# combined_breakout.net
KiCad netlist of a schematic drawn in EAGLE
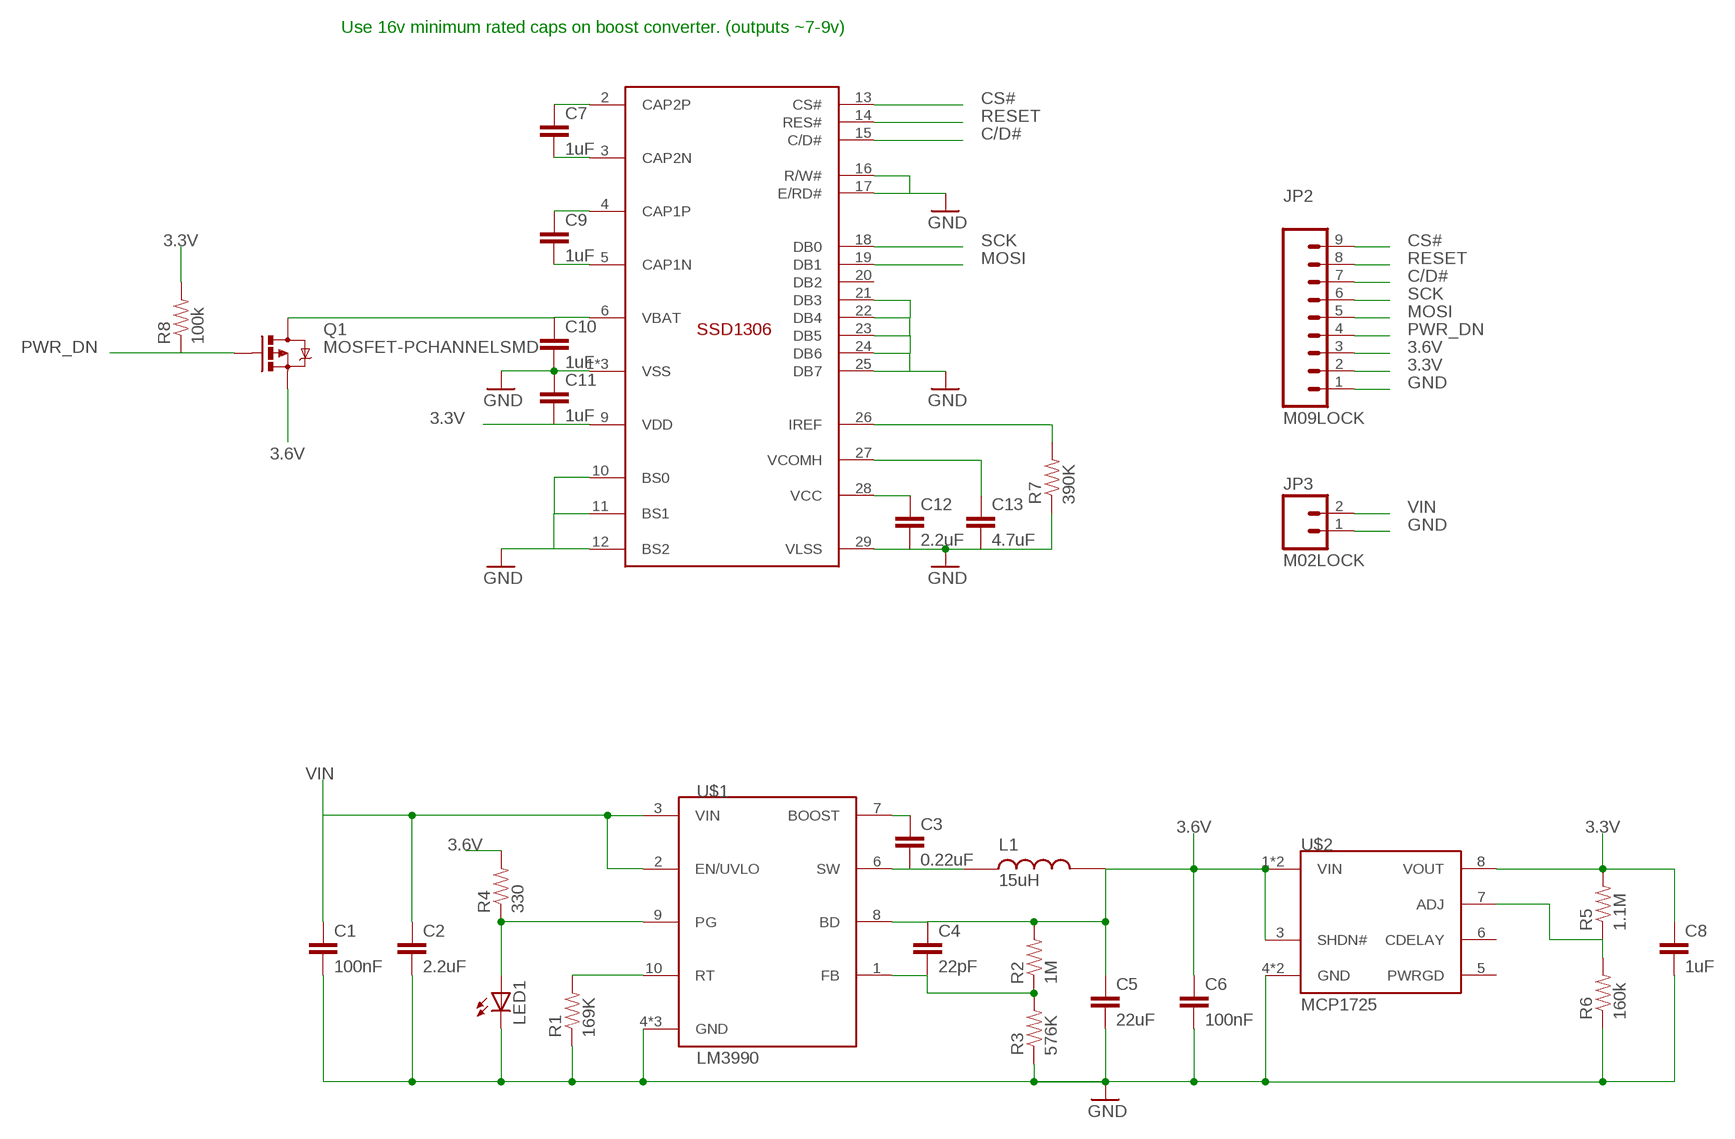
[diagram p0: schematic, sheet 1]

(export (version "E")
  (design (tool "Eeschema 10.0.6"))
  (components
    (comp (ref "C1")
      (value "100nF")
      (footprint "eagle-import:0603-CAP")
      (libsource (lib "eagle-import") (part "CAP0603-CAP"))
    )
    (comp (ref "C2")
      (value "2.2uF")
      (footprint "eagle-import:1206")
      (libsource (lib "eagle-import") (part "CAP1206"))
    )
    (comp (ref "C3")
      (value "0.22uF")
      (footprint "eagle-import:0603-CAP")
      (libsource (lib "eagle-import") (part "CAP0603-CAP"))
    )
    (comp (ref "C4")
      (value "22pF")
      (footprint "eagle-import:0603-CAP")
      (libsource (lib "eagle-import") (part "CAP0603-CAP"))
    )
    (comp (ref "C5")
      (value "22uF")
      (footprint "eagle-import:1206")
      (libsource (lib "eagle-import") (part "CAP1206"))
    )
    (comp (ref "C6")
      (value "100nF")
      (footprint "eagle-import:0603-CAP")
      (libsource (lib "eagle-import") (part "CAP0603-CAP"))
    )
    (comp (ref "C7")
      (value "1uF")
      (footprint "eagle-import:0402-S")
      (libsource (lib "eagle-import") (part "CAP0402-S"))
    )
    (comp (ref "C8")
      (value "1uF")
      (footprint "eagle-import:0603-CAP")
      (libsource (lib "eagle-import") (part "CAP0603-CAP"))
    )
    (comp (ref "C9")
      (value "1uF")
      (footprint "eagle-import:0402-S")
      (libsource (lib "eagle-import") (part "CAP0402-S"))
    )
    (comp (ref "C10")
      (value "1uF")
      (footprint "eagle-import:0402-S")
      (libsource (lib "eagle-import") (part "CAP0402-S"))
    )
    (comp (ref "C11")
      (value "1uF")
      (footprint "eagle-import:0402-S")
      (libsource (lib "eagle-import") (part "CAP0402-S"))
    )
    (comp (ref "C12")
      (value "2.2uF")
      (footprint "eagle-import:0402-S")
      (libsource (lib "eagle-import") (part "CAP0402-S"))
    )
    (comp (ref "C13")
      (value "4.7uF")
      (footprint "eagle-import:0402-S")
      (libsource (lib "eagle-import") (part "CAP0402-S"))
    )
    (comp (ref "JP2")
      (value "M09LOCK")
      (footprint "eagle-import:1X09_LOCK")
      (libsource (lib "eagle-import") (part "M09LOCK"))
    )
    (comp (ref "JP3")
      (value "M02LOCK")
      (footprint "eagle-import:1X02_LOCK")
      (libsource (lib "eagle-import") (part "M02LOCK"))
    )
    (comp (ref "L1")
      (value "15uH")
      (footprint "eagle-import:NR6028T150M")
      (libsource (lib "eagle-import") (part "NR6028T150M"))
    )
    (comp (ref "LED1")
      (value "LED0603")
      (footprint "eagle-import:LED-0603")
      (libsource (lib "eagle-import") (part "LED0603"))
    )
    (comp (ref "Q1")
      (value "MOSFET-PCHANNELSMD")
      (footprint "eagle-import:SOT23-3")
      (libsource (lib "eagle-import") (part "MOSFET-PCHANNELSMD"))
    )
    (comp (ref "R1")
      (value "169K")
      (footprint "eagle-import:0402-S")
      (libsource (lib "eagle-import") (part "RESISTOR0402-S"))
    )
    (comp (ref "R2")
      (value "1M")
      (footprint "eagle-import:0402-S")
      (libsource (lib "eagle-import") (part "RESISTOR0402-S"))
    )
    (comp (ref "R3")
      (value "576K")
      (footprint "eagle-import:0402-S")
      (libsource (lib "eagle-import") (part "RESISTOR0402-S"))
    )
    (comp (ref "R4")
      (value "330")
      (footprint "eagle-import:0402-S")
      (libsource (lib "eagle-import") (part "RESISTOR0402-S"))
    )
    (comp (ref "R5")
      (value "1.1M")
      (footprint "eagle-import:0402-S")
      (libsource (lib "eagle-import") (part "RESISTOR0402-S"))
    )
    (comp (ref "R6")
      (value "160k")
      (footprint "eagle-import:0402-S")
      (libsource (lib "eagle-import") (part "RESISTOR0402-S"))
    )
    (comp (ref "R7")
      (value "390K")
      (footprint "eagle-import:0402-S")
      (libsource (lib "eagle-import") (part "RESISTOR0402-S"))
    )
    (comp (ref "R8")
      (value "100k")
      (footprint "eagle-import:0402-S")
      (libsource (lib "eagle-import") (part "RESISTOR0402-S"))
    )
    (comp (ref "U$1")
      (value "LM3990")
      (footprint "eagle-import:DD10")
      (libsource (lib "eagle-import") (part "LM3990"))
    )
    (comp (ref "U$2")
      (value "MCP1725")
      (footprint "eagle-import:2X3_DFN")
      (libsource (lib "eagle-import") (part "MCP1725"))
    )
    (comp (ref "U$3")
      (value "ER-OLED0.96-2")
      (footprint "eagle-import:ER-OLED0.96-2")
      (libsource (lib "eagle-import") (part "ER-OLED0.96-2"))
    )
  )
  (nets
    (net (code "1") (name "/3.3V") (class "Default")
      (node (ref "C11") (pin "2") (pinfunction "2_2") (pintype "passive"))
      (node (ref "C8") (pin "1") (pinfunction "1_1") (pintype "passive"))
      (node (ref "JP2") (pin "2") (pinfunction "2_2") (pintype "passive"))
      (node (ref "R5") (pin "2") (pinfunction "2_2") (pintype "passive"))
      (node (ref "R8") (pin "2") (pinfunction "2_2") (pintype "passive"))
      (node (ref "U$2") (pin "8") (pinfunction "VOUT_8") (pintype "bidirectional"))
      (node (ref "U$3") (pin "9") (pinfunction "VDD_9") (pintype "power_in"))
    )
    (net (code "2") (name "/3.6V") (class "Default")
      (node (ref "C4") (pin "1") (pinfunction "1_1") (pintype "passive"))
      (node (ref "C5") (pin "1") (pinfunction "1_1") (pintype "passive"))
      (node (ref "C6") (pin "1") (pinfunction "1_1") (pintype "passive"))
      (node (ref "JP2") (pin "3") (pinfunction "3_3") (pintype "passive"))
      (node (ref "L1") (pin "2") (pinfunction "2_2") (pintype "bidirectional"))
      (node (ref "Q1") (pin "2") (pinfunction "S_2") (pintype "passive"))
      (node (ref "R2") (pin "2") (pinfunction "2_2") (pintype "passive"))
      (node (ref "R4") (pin "2") (pinfunction "2_2") (pintype "passive"))
      (node (ref "U$1") (pin "8") (pinfunction "BD_8") (pintype "bidirectional"))
      (node (ref "U$2") (pin "1") (pinfunction "VIN_1") (pintype "bidirectional"))
      (node (ref "U$2") (pin "2") (pinfunction "VIN_2") (pintype "bidirectional"))
      (node (ref "U$2") (pin "3") (pinfunction "SHDN#_3") (pintype "bidirectional"))
    )
    (net (code "3") (name "/CS#") (class "Default")
      (node (ref "JP2") (pin "9") (pinfunction "9_9") (pintype "passive"))
      (node (ref "U$3") (pin "13") (pinfunction "CS#_13") (pintype "bidirectional"))
    )
    (net (code "4") (name "/C{slash}D#") (class "Default")
      (node (ref "JP2") (pin "7") (pinfunction "7_7") (pintype "passive"))
      (node (ref "U$3") (pin "15") (pinfunction "C/D#_15") (pintype "bidirectional"))
    )
    (net (code "5") (name "/MOSI") (class "Default")
      (node (ref "JP2") (pin "5") (pinfunction "5_5") (pintype "passive"))
      (node (ref "U$3") (pin "19") (pinfunction "DB1_19") (pintype "bidirectional"))
    )
    (net (code "6") (name "/PWR_DN") (class "Default")
      (node (ref "JP2") (pin "4") (pinfunction "4_4") (pintype "passive"))
      (node (ref "Q1") (pin "1") (pinfunction "G_1") (pintype "passive"))
      (node (ref "R8") (pin "1") (pinfunction "1_1") (pintype "passive"))
    )
    (net (code "7") (name "/RESET") (class "Default")
      (node (ref "JP2") (pin "8") (pinfunction "8_8") (pintype "passive"))
      (node (ref "U$3") (pin "14") (pinfunction "RES#_14") (pintype "bidirectional"))
    )
    (net (code "8") (name "/SCK") (class "Default")
      (node (ref "JP2") (pin "6") (pinfunction "6_6") (pintype "passive"))
      (node (ref "U$3") (pin "18") (pinfunction "DB0_18") (pintype "bidirectional"))
    )
    (net (code "9") (name "/VIN") (class "Default")
      (node (ref "C1") (pin "1") (pinfunction "1_1") (pintype "passive"))
      (node (ref "C2") (pin "1") (pinfunction "1_1") (pintype "passive"))
      (node (ref "JP3") (pin "2") (pinfunction "2_2") (pintype "passive"))
      (node (ref "U$1") (pin "2") (pinfunction "EN/UVLO_2") (pintype "bidirectional"))
      (node (ref "U$1") (pin "3") (pinfunction "VIN_3") (pintype "bidirectional"))
    )
    (net (code "10") (name "GND") (class "Default")
      (node (ref "C1") (pin "2") (pinfunction "2_2") (pintype "passive"))
      (node (ref "C10") (pin "2") (pinfunction "2_2") (pintype "passive"))
      (node (ref "C11") (pin "1") (pinfunction "1_1") (pintype "passive"))
      (node (ref "C12") (pin "2") (pinfunction "2_2") (pintype "passive"))
      (node (ref "C13") (pin "2") (pinfunction "2_2") (pintype "passive"))
      (node (ref "C2") (pin "2") (pinfunction "2_2") (pintype "passive"))
      (node (ref "C5") (pin "2") (pinfunction "2_2") (pintype "passive"))
      (node (ref "C6") (pin "2") (pinfunction "2_2") (pintype "passive"))
      (node (ref "C8") (pin "2") (pinfunction "2_2") (pintype "passive"))
      (node (ref "JP2") (pin "1") (pinfunction "1_1") (pintype "passive"))
      (node (ref "JP3") (pin "1") (pinfunction "1_1") (pintype "passive"))
      (node (ref "LED1") (pin "C") (pinfunction "C_C") (pintype "passive"))
      (node (ref "R1") (pin "1") (pinfunction "1_1") (pintype "passive"))
      (node (ref "R3") (pin "1") (pinfunction "1_1") (pintype "passive"))
      (node (ref "R6") (pin "1") (pinfunction "1_1") (pintype "passive"))
      (node (ref "R7") (pin "1") (pinfunction "1_1") (pintype "passive"))
      (node (ref "U$1") (pin "4") (pinfunction "GND_4") (pintype "bidirectional"))
      (node (ref "U$1") (pin "5") (pinfunction "GND_5") (pintype "bidirectional"))
      (node (ref "U$1") (pin "EP\\") (pinfunction "GND_EP\\") (pintype "bidirectional"))
      (node (ref "U$2") (pin "4") (pinfunction "GND_4") (pintype "bidirectional"))
      (node (ref "U$2") (pin "EP") (pinfunction "GND_EP") (pintype "bidirectional"))
      (node (ref "U$3") (pin "1") (pinfunction "VSS_1") (pintype "power_in"))
      (node (ref "U$3") (pin "10") (pinfunction "BS0_10") (pintype "bidirectional"))
      (node (ref "U$3") (pin "11") (pinfunction "BS1_11") (pintype "bidirectional"))
      (node (ref "U$3") (pin "12") (pinfunction "BS2_12") (pintype "bidirectional"))
      (node (ref "U$3") (pin "16") (pinfunction "R/W#_16") (pintype "bidirectional"))
      (node (ref "U$3") (pin "17") (pinfunction "E/RD#_17") (pintype "bidirectional"))
      (node (ref "U$3") (pin "21") (pinfunction "DB3_21") (pintype "bidirectional"))
      (node (ref "U$3") (pin "22") (pinfunction "DB4_22") (pintype "bidirectional"))
      (node (ref "U$3") (pin "23") (pinfunction "DB5_23") (pintype "bidirectional"))
      (node (ref "U$3") (pin "24") (pinfunction "DB6_24") (pintype "bidirectional"))
      (node (ref "U$3") (pin "25") (pinfunction "DB7_25") (pintype "bidirectional"))
      (node (ref "U$3") (pin "29") (pinfunction "VLSS_29") (pintype "power_in"))
      (node (ref "U$3") (pin "30") (pinfunction "VSS_30") (pintype "power_in"))
      (node (ref "U$3") (pin "8") (pinfunction "VSS_8") (pintype "power_in"))
    )
    (net (code "11") (name "Net-(Q1-D)") (class "Default")
      (node (ref "C10") (pin "1") (pinfunction "1_1") (pintype "passive"))
      (node (ref "Q1") (pin "3") (pinfunction "D_3") (pintype "passive"))
      (node (ref "U$3") (pin "6") (pinfunction "VBAT_6") (pintype "power_in"))
    )
    (net (code "12") (name "Net-(U$1-BOOST)") (class "Default")
      (node (ref "C3") (pin "1") (pinfunction "1_1") (pintype "passive"))
      (node (ref "U$1") (pin "7") (pinfunction "BOOST_7") (pintype "bidirectional"))
    )
    (net (code "13") (name "Net-(U$1-FB)") (class "Default")
      (node (ref "C4") (pin "2") (pinfunction "2_2") (pintype "passive"))
      (node (ref "R2") (pin "1") (pinfunction "1_1") (pintype "passive"))
      (node (ref "R3") (pin "2") (pinfunction "2_2") (pintype "passive"))
      (node (ref "U$1") (pin "1") (pinfunction "FB_1") (pintype "bidirectional"))
    )
    (net (code "14") (name "Net-(U$1-PG)") (class "Default")
      (node (ref "LED1") (pin "A") (pinfunction "A_A") (pintype "passive"))
      (node (ref "R4") (pin "1") (pinfunction "1_1") (pintype "passive"))
      (node (ref "U$1") (pin "9") (pinfunction "PG_9") (pintype "bidirectional"))
    )
    (net (code "15") (name "Net-(U$1-RT)") (class "Default")
      (node (ref "R1") (pin "2") (pinfunction "2_2") (pintype "passive"))
      (node (ref "U$1") (pin "10") (pinfunction "RT_10") (pintype "bidirectional"))
    )
    (net (code "16") (name "Net-(U$1-SW)") (class "Default")
      (node (ref "C3") (pin "2") (pinfunction "2_2") (pintype "passive"))
      (node (ref "L1") (pin "1") (pinfunction "1_1") (pintype "bidirectional"))
      (node (ref "U$1") (pin "6") (pinfunction "SW_6") (pintype "bidirectional"))
    )
    (net (code "17") (name "Net-(U$2-ADJ)") (class "Default")
      (node (ref "R5") (pin "1") (pinfunction "1_1") (pintype "passive"))
      (node (ref "R6") (pin "2") (pinfunction "2_2") (pintype "passive"))
      (node (ref "U$2") (pin "7") (pinfunction "ADJ_7") (pintype "bidirectional"))
    )
    (net (code "18") (name "Net-(U$3-CAP1N)") (class "Default")
      (node (ref "C9") (pin "2") (pinfunction "2_2") (pintype "passive"))
      (node (ref "U$3") (pin "5") (pinfunction "CAP1N_5") (pintype "power_in"))
    )
    (net (code "19") (name "Net-(U$3-CAP1P)") (class "Default")
      (node (ref "C9") (pin "1") (pinfunction "1_1") (pintype "passive"))
      (node (ref "U$3") (pin "4") (pinfunction "CAP1P_4") (pintype "power_in"))
    )
    (net (code "20") (name "Net-(U$3-CAP2N)") (class "Default")
      (node (ref "C7") (pin "2") (pinfunction "2_2") (pintype "passive"))
      (node (ref "U$3") (pin "3") (pinfunction "CAP2N_3") (pintype "power_in"))
    )
    (net (code "21") (name "Net-(U$3-CAP2P)") (class "Default")
      (node (ref "C7") (pin "1") (pinfunction "1_1") (pintype "passive"))
      (node (ref "U$3") (pin "2") (pinfunction "CAP2P_2") (pintype "power_in"))
    )
    (net (code "22") (name "Net-(U$3-IREF)") (class "Default")
      (node (ref "R7") (pin "2") (pinfunction "2_2") (pintype "passive"))
      (node (ref "U$3") (pin "26") (pinfunction "IREF_26") (pintype "power_in"))
    )
    (net (code "23") (name "Net-(U$3-VCC)") (class "Default")
      (node (ref "C12") (pin "1") (pinfunction "1_1") (pintype "passive"))
      (node (ref "U$3") (pin "28") (pinfunction "VCC_28") (pintype "power_in"))
    )
    (net (code "24") (name "Net-(U$3-VCOMH)") (class "Default")
      (node (ref "C13") (pin "1") (pinfunction "1_1") (pintype "passive"))
      (node (ref "U$3") (pin "27") (pinfunction "VCOMH_27") (pintype "power_in"))
    )
    (net (code "25") (name "unconnected-(U$2-CDELAY-Pad6)") (class "Default")
      (node (ref "U$2") (pin "6") (pinfunction "CDELAY_6") (pintype "bidirectional"))
    )
    (net (code "26") (name "unconnected-(U$2-PWRGD-Pad5)") (class "Default")
      (node (ref "U$2") (pin "5") (pinfunction "PWRGD_5") (pintype "bidirectional"))
    )
    (net (code "27") (name "unconnected-(U$3-DB2-Pad20)") (class "Default")
      (node (ref "U$3") (pin "20") (pinfunction "DB2_20") (pintype "bidirectional"))
    )
  )
)
